# FT2232D.net
KiCad netlist of a schematic drawn in Altium Designer
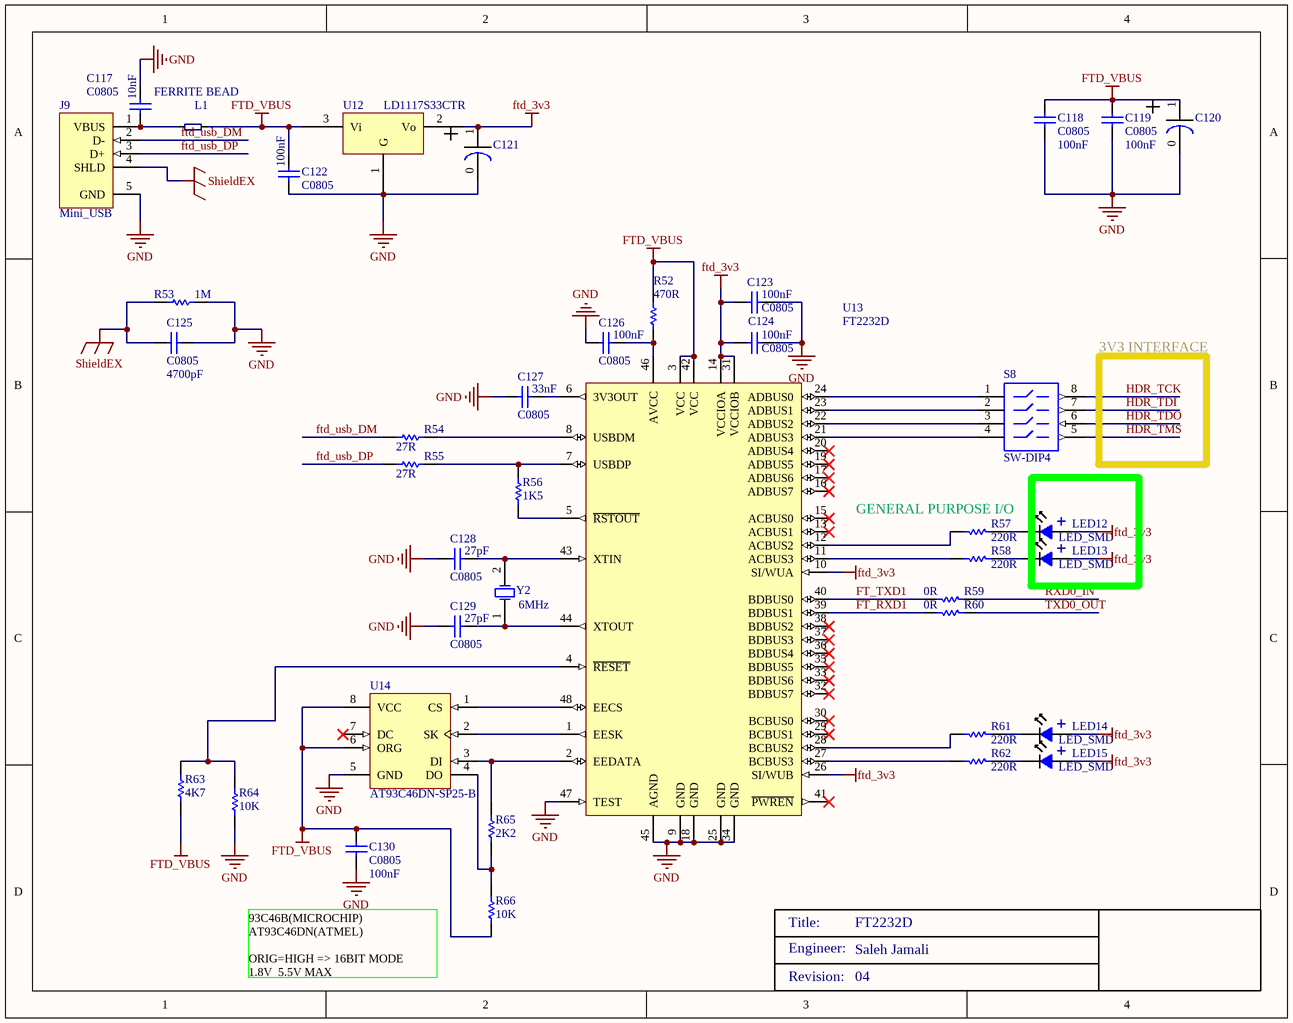
[diagram p0: FT2232D.SchDoc]

(export (version "E")
  (design (tool "Eeschema 10.0.6"))
  (components
    (comp (ref "C117")
      (value "C0805")
      (footprint "0805")
      (description "Ceramic Chip Capacitor - Standard")
      (fields (field (name "ALTIUM_VALUE") "10nF") (field (name "PUBLISHER") "Altium Limited"))
      (libsource (lib "KEMET Chip Capacitor") (part "C0805"))
    )
    (comp (ref "C118")
      (value "C0805")
      (footprint "0805")
      (description "Ceramic Chip Capacitor - Standard")
      (fields (field (name "ALTIUM_VALUE") "100nF") (field (name "PUBLISHER") "Altium Limited"))
      (libsource (lib "KEMET Chip Capacitor") (part "C0805"))
    )
    (comp (ref "C119")
      (value "C0805")
      (footprint "0805")
      (description "Ceramic Chip Capacitor - Standard")
      (fields (field (name "ALTIUM_VALUE") "100nF") (field (name "PUBLISHER") "Altium Limited"))
      (libsource (lib "KEMET Chip Capacitor") (part "C0805"))
    )
    (comp (ref "C120")
      (value "Electrolytic SMD Cap")
      (footprint "22_47u_10A")
      (libsource (lib "SMD_ELECTRLT_CAP") (part "Electrolytic SMD Cap"))
    )
    (comp (ref "C121")
      (value "Electrolytic SMD Cap")
      (footprint "22_47u_10A")
      (libsource (lib "SMD_ELECTRLT_CAP") (part "Electrolytic SMD Cap"))
    )
    (comp (ref "C122")
      (value "C0805")
      (footprint "0805")
      (description "Ceramic Chip Capacitor - Standard")
      (fields (field (name "ALTIUM_VALUE") "100nF") (field (name "PUBLISHER") "Altium Limited"))
      (libsource (lib "KEMET Chip Capacitor") (part "C0805"))
    )
    (comp (ref "C123")
      (value "C0805")
      (footprint "0805")
      (description "Ceramic Chip Capacitor - Standard")
      (fields (field (name "ALTIUM_VALUE") "100nF") (field (name "PUBLISHER") "Altium Limited"))
      (libsource (lib "KEMET Chip Capacitor") (part "C0805"))
    )
    (comp (ref "C124")
      (value "C0805")
      (footprint "0805")
      (description "Ceramic Chip Capacitor - Standard")
      (fields (field (name "ALTIUM_VALUE") "100nF") (field (name "PUBLISHER") "Altium Limited"))
      (libsource (lib "KEMET Chip Capacitor") (part "C0805"))
    )
    (comp (ref "C125")
      (value "C0805")
      (footprint "0805")
      (description "Ceramic Chip Capacitor - Standard")
      (fields (field (name "ALTIUM_VALUE") "4700pF") (field (name "PUBLISHER") "Altium Limited"))
      (libsource (lib "KEMET Chip Capacitor") (part "C0805"))
    )
    (comp (ref "C126")
      (value "C0805")
      (footprint "0805")
      (description "Ceramic Chip Capacitor - Standard")
      (fields (field (name "ALTIUM_VALUE") "100nF") (field (name "PUBLISHER") "Altium Limited"))
      (libsource (lib "KEMET Chip Capacitor") (part "C0805"))
    )
    (comp (ref "C127")
      (value "C0805")
      (footprint "0805")
      (description "Ceramic Chip Capacitor - Standard")
      (fields (field (name "ALTIUM_VALUE") "33nF") (field (name "PUBLISHER") "Altium Limited"))
      (libsource (lib "KEMET Chip Capacitor") (part "C0805"))
    )
    (comp (ref "C128")
      (value "C0805")
      (footprint "0805")
      (description "Ceramic Chip Capacitor - Standard")
      (fields (field (name "ALTIUM_VALUE") "27pF") (field (name "PUBLISHER") "Altium Limited"))
      (libsource (lib "KEMET Chip Capacitor") (part "C0805"))
    )
    (comp (ref "C129")
      (value "C0805")
      (footprint "0805")
      (description "Ceramic Chip Capacitor - Standard")
      (fields (field (name "ALTIUM_VALUE") "27pF") (field (name "PUBLISHER") "Altium Limited"))
      (libsource (lib "KEMET Chip Capacitor") (part "C0805"))
    )
    (comp (ref "C130")
      (value "C0805")
      (footprint "0805")
      (description "Ceramic Chip Capacitor - Standard")
      (fields (field (name "ALTIUM_VALUE") "100nF") (field (name "PUBLISHER") "Altium Limited"))
      (libsource (lib "KEMET Chip Capacitor") (part "C0805"))
    )
    (comp (ref "J9")
      (value "Mini_USB")
      (footprint "My_USB")
      (description "USB 2.0, Right Angle, SMT, B Type, Receptacle, 5 Position, Black")
      (fields (field (name "PUBLISHER") "Altium Limited"))
      (libsource (lib "Mylib") (part "Mini_USB"))
    )
    (comp (ref "L1")
      (value "FERRITE BEAD")
      (footprint "smd_ferrite_1206")
      (libsource (lib "FERRITE_PRJCT") (part "FERRITE BEAD"))
    )
    (comp (ref "LED12")
      (value "LED_SMD")
      (footprint "LED_805")
      (libsource (lib "LED_PRJCT") (part "LED_SMD"))
    )
    (comp (ref "LED13")
      (value "LED_SMD")
      (footprint "LED_805")
      (libsource (lib "LED_PRJCT") (part "LED_SMD"))
    )
    (comp (ref "LED14")
      (value "LED_SMD")
      (footprint "LED_805")
      (libsource (lib "LED_PRJCT") (part "LED_SMD"))
    )
    (comp (ref "LED15")
      (value "LED_SMD")
      (footprint "LED_805")
      (libsource (lib "LED_PRJCT") (part "LED_SMD"))
    )
    (comp (ref "R52")
      (value "470R")
      (footprint "ERA-0805")
      (fields (field (name "PUBLISHER") "Altium Limited"))
      (libsource (lib "Panasonic Resistor") (part "ERA6Y"))
    )
    (comp (ref "R53")
      (value "1M")
      (footprint "ERA-0805")
      (fields (field (name "PUBLISHER") "Altium Limited"))
      (libsource (lib "Panasonic Resistor") (part "ERA6Y"))
    )
    (comp (ref "R54")
      (value "27R")
      (footprint "ERA-0805")
      (fields (field (name "PUBLISHER") "Altium Limited"))
      (libsource (lib "Panasonic Resistor") (part "ERA6Y"))
    )
    (comp (ref "R55")
      (value "27R")
      (footprint "ERA-0805")
      (fields (field (name "PUBLISHER") "Altium Limited"))
      (libsource (lib "Panasonic Resistor") (part "ERA6Y"))
    )
    (comp (ref "R56")
      (value "1K5")
      (footprint "ERA-0805")
      (fields (field (name "PUBLISHER") "Altium Limited"))
      (libsource (lib "Panasonic Resistor") (part "ERA6Y"))
    )
    (comp (ref "R57")
      (value "220R")
      (footprint "ERA-0805")
      (fields (field (name "PUBLISHER") "Altium Limited"))
      (libsource (lib "Panasonic Resistor") (part "ERA6Y"))
    )
    (comp (ref "R58")
      (value "220R")
      (footprint "ERA-0805")
      (fields (field (name "PUBLISHER") "Altium Limited"))
      (libsource (lib "Panasonic Resistor") (part "ERA6Y"))
    )
    (comp (ref "R59")
      (value "0R")
      (footprint "ERA-0805")
      (fields (field (name "PUBLISHER") "Altium Limited"))
      (libsource (lib "Panasonic Resistor") (part "ERA6Y"))
    )
    (comp (ref "R60")
      (value "0R")
      (footprint "ERA-0805")
      (fields (field (name "PUBLISHER") "Altium Limited"))
      (libsource (lib "Panasonic Resistor") (part "ERA6Y"))
    )
    (comp (ref "R61")
      (value "220R")
      (footprint "ERA-0805")
      (fields (field (name "PUBLISHER") "Altium Limited"))
      (libsource (lib "Panasonic Resistor") (part "ERA6Y"))
    )
    (comp (ref "R62")
      (value "220R")
      (footprint "ERA-0805")
      (fields (field (name "PUBLISHER") "Altium Limited"))
      (libsource (lib "Panasonic Resistor") (part "ERA6Y"))
    )
    (comp (ref "R63")
      (value "4K7")
      (footprint "ERA-0805")
      (fields (field (name "PUBLISHER") "Altium Limited"))
      (libsource (lib "Panasonic Resistor") (part "ERA6Y"))
    )
    (comp (ref "R64")
      (value "10K")
      (footprint "ERA-0805")
      (fields (field (name "PUBLISHER") "Altium Limited"))
      (libsource (lib "Panasonic Resistor") (part "ERA6Y"))
    )
    (comp (ref "R65")
      (value "2K2")
      (footprint "ERA-0805")
      (fields (field (name "PUBLISHER") "Altium Limited"))
      (libsource (lib "Panasonic Resistor") (part "ERA6Y"))
    )
    (comp (ref "R66")
      (value "10K")
      (footprint "ERA-0805")
      (fields (field (name "PUBLISHER") "Altium Limited"))
      (libsource (lib "Panasonic Resistor") (part "ERA6Y"))
    )
    (comp (ref "S8")
      (value "SW-DIP4")
      (footprint "DIP-8")
      (description "DIP Switch")
      (fields (field (name "PUBLISHER") "Altium Limited"))
      (libsource (lib "Miscellaneous Devices") (part "SW-DIP4"))
    )
    (comp (ref "U12")
      (value "LD1117S33CTR")
      (footprint "SOT223")
      (description "2.5 volt, 800mA Regulator")
      (libsource (lib "LD1117S25_SOT223") (part "LD1117S33CTR"))
    )
    (comp (ref "U13")
      (value "FT2232D")
      (footprint "LQFP-48_M")
      (description "FT2232D Dual USB to Serial UART/FIFO IC, -40 to +85 degC, 48-pin LQFP")
      (fields (field (name "MANUFACTURER") "FTDI"))
      (libsource (lib "FTDI FT Series") (part "FT2232D"))
    )
    (comp (ref "U14")
      (value "AT93C46DN-SP25-B")
      (footprint "8S1_M")
      (description "1Kbit (128 x 8 or 64 x 16), 3-wire Bus Serial Automotive EEPROM, 2.5V, 8-Pin SOIC, Bulk")
      (libsource (lib "Atmel Serial EEPROM") (part "AT93C46DN-SP25-B"))
    )
    (comp (ref "Y2")
      (value "6MHz")
      (footprint "HC-49U")
      (description "Crystal Oscillator")
      (fields (field (name "PUBLISHER") "Altium Limited"))
      (libsource (lib "ECS Crystal Oscillator") (part "ECS-18-13-1"))
    )
  )
  (nets
    (net (code "1") (name "/FT_RXD1") (class "Default")
      (node (ref "R60") (pin "2") (pinfunction "2_2") (pintype "passive"))
      (node (ref "U13") (pin "39") (pinfunction "BDBUS1_39") (pintype "bidirectional"))
    )
    (net (code "2") (name "/FT_TXD1") (class "Default")
      (node (ref "R59") (pin "2") (pinfunction "2_2") (pintype "passive"))
      (node (ref "U13") (pin "40") (pinfunction "BDBUS0_40") (pintype "bidirectional"))
    )
    (net (code "3") (name "/HDR_TCK") (class "Default")
      (node (ref "S8") (pin "8") (pinfunction "8_8") (pintype "output"))
    )
    (net (code "4") (name "/HDR_TDI") (class "Default")
      (node (ref "S8") (pin "7") (pinfunction "7_7") (pintype "output"))
    )
    (net (code "5") (name "/HDR_TDO") (class "Default")
      (node (ref "S8") (pin "6") (pinfunction "6_6") (pintype "input"))
    )
    (net (code "6") (name "/HDR_TMS") (class "Default")
      (node (ref "S8") (pin "5") (pinfunction "5_5") (pintype "output"))
    )
    (net (code "7") (name "/RXD0_IN") (class "Default")
      (node (ref "R59") (pin "1") (pinfunction "1_1") (pintype "passive"))
    )
    (net (code "8") (name "/TXD0_OUT") (class "Default")
      (node (ref "R60") (pin "1") (pinfunction "1_1") (pintype "passive"))
    )
    (net (code "9") (name "/ftd_usb_DM") (class "Default")
      (node (ref "J9") (pin "2") (pinfunction "D-_2") (pintype "input"))
      (node (ref "R54") (pin "2") (pinfunction "2_2") (pintype "passive"))
    )
    (net (code "10") (name "/ftd_usb_DP") (class "Default")
      (node (ref "J9") (pin "3") (pinfunction "D+_3") (pintype "input"))
      (node (ref "R55") (pin "2") (pinfunction "2_2") (pintype "passive"))
    )
    (net (code "11") (name "FTD_VBUS") (class "Default")
      (node (ref "C118") (pin "2") (pinfunction "2_2") (pintype "passive"))
      (node (ref "C119") (pin "2") (pinfunction "2_2") (pintype "passive"))
      (node (ref "C120") (pin "1") (pinfunction "1_1") (pintype "passive"))
      (node (ref "C122") (pin "1") (pinfunction "1_1") (pintype "passive"))
      (node (ref "C130") (pin "2") (pinfunction "2_2") (pintype "passive"))
      (node (ref "L1") (pin "1") (pinfunction "1_1") (pintype "passive"))
      (node (ref "R52") (pin "1") (pinfunction "1_1") (pintype "passive"))
      (node (ref "R63") (pin "1") (pinfunction "1_1") (pintype "passive"))
      (node (ref "R66") (pin "1") (pinfunction "1_1") (pintype "passive"))
      (node (ref "U12") (pin "3") (pinfunction "Vi_3") (pintype "power_in"))
      (node (ref "U13") (pin "3") (pinfunction "VCC_3") (pintype "power_in"))
      (node (ref "U13") (pin "42") (pinfunction "VCC_42") (pintype "power_in"))
      (node (ref "U14") (pin "6") (pinfunction "ORG_6") (pintype "input"))
      (node (ref "U14") (pin "8") (pinfunction "VCC_8") (pintype "power_in"))
    )
    (net (code "12") (name "GND") (class "Default")
      (node (ref "C117") (pin "1") (pinfunction "1_1") (pintype "passive"))
      (node (ref "C118") (pin "1") (pinfunction "1_1") (pintype "passive"))
      (node (ref "C119") (pin "1") (pinfunction "1_1") (pintype "passive"))
      (node (ref "C120") (pin "0") (pinfunction "0_0") (pintype "passive"))
      (node (ref "C121") (pin "0") (pinfunction "0_0") (pintype "passive"))
      (node (ref "C122") (pin "2") (pinfunction "2_2") (pintype "passive"))
      (node (ref "C123") (pin "2") (pinfunction "2_2") (pintype "passive"))
      (node (ref "C124") (pin "2") (pinfunction "2_2") (pintype "passive"))
      (node (ref "C125") (pin "2") (pinfunction "2_2") (pintype "passive"))
      (node (ref "C126") (pin "1") (pinfunction "1_1") (pintype "passive"))
      (node (ref "C127") (pin "1") (pinfunction "1_1") (pintype "passive"))
      (node (ref "C128") (pin "1") (pinfunction "1_1") (pintype "passive"))
      (node (ref "C129") (pin "1") (pinfunction "1_1") (pintype "passive"))
      (node (ref "C130") (pin "1") (pinfunction "1_1") (pintype "passive"))
      (node (ref "J9") (pin "5") (pinfunction "GND_5") (pintype "passive"))
      (node (ref "R53") (pin "1") (pinfunction "1_1") (pintype "passive"))
      (node (ref "R64") (pin "1") (pinfunction "1_1") (pintype "passive"))
      (node (ref "U12") (pin "1") (pinfunction "G_1") (pintype "power_in"))
      (node (ref "U13") (pin "18") (pinfunction "GND_18") (pintype "power_in"))
      (node (ref "U13") (pin "25") (pinfunction "GND_25") (pintype "power_in"))
      (node (ref "U13") (pin "34") (pinfunction "GND_34") (pintype "power_in"))
      (node (ref "U13") (pin "45") (pinfunction "AGND_45") (pintype "power_in"))
      (node (ref "U13") (pin "47") (pinfunction "TEST_47") (pintype "input"))
      (node (ref "U13") (pin "9") (pinfunction "GND_9") (pintype "power_in"))
      (node (ref "U14") (pin "5") (pinfunction "GND_5") (pintype "power_in"))
    )
    (net (code "13") (name "Net-(J9-VBUS)") (class "Default")
      (node (ref "C117") (pin "2") (pinfunction "2_2") (pintype "passive"))
      (node (ref "J9") (pin "1") (pinfunction "VBUS_1") (pintype "power_in"))
      (node (ref "L1") (pin "0") (pinfunction "0_0") (pintype "passive"))
    )
    (net (code "14") (name "Net-(LED12-Pad2)") (class "Default")
      (node (ref "LED12") (pin "2") (pinfunction "2_2") (pintype "passive"))
      (node (ref "R57") (pin "1") (pinfunction "1_1") (pintype "passive"))
    )
    (net (code "15") (name "Net-(LED13-Pad2)") (class "Default")
      (node (ref "LED13") (pin "2") (pinfunction "2_2") (pintype "passive"))
      (node (ref "R58") (pin "1") (pinfunction "1_1") (pintype "passive"))
    )
    (net (code "16") (name "Net-(LED14-Pad2)") (class "Default")
      (node (ref "LED14") (pin "2") (pinfunction "2_2") (pintype "passive"))
      (node (ref "R61") (pin "1") (pinfunction "1_1") (pintype "passive"))
    )
    (net (code "17") (name "Net-(LED15-Pad2)") (class "Default")
      (node (ref "LED15") (pin "2") (pinfunction "2_2") (pintype "passive"))
      (node (ref "R62") (pin "1") (pinfunction "1_1") (pintype "passive"))
    )
    (net (code "18") (name "Net-(U13-3V3OUT)") (class "Default")
      (node (ref "C127") (pin "2") (pinfunction "2_2") (pintype "passive"))
      (node (ref "U13") (pin "6") (pinfunction "3V3OUT_6") (pintype "output"))
    )
    (net (code "19") (name "Net-(U13-ACBUS2)") (class "Default")
      (node (ref "R57") (pin "2") (pinfunction "2_2") (pintype "passive"))
      (node (ref "U13") (pin "12") (pinfunction "ACBUS2_12") (pintype "bidirectional"))
    )
    (net (code "20") (name "Net-(U13-ACBUS3)") (class "Default")
      (node (ref "R58") (pin "2") (pinfunction "2_2") (pintype "passive"))
      (node (ref "U13") (pin "11") (pinfunction "ACBUS3_11") (pintype "bidirectional"))
    )
    (net (code "21") (name "Net-(U13-ADBUS0)") (class "Default")
      (node (ref "S8") (pin "1") (pinfunction "1_1") (pintype "passive"))
      (node (ref "U13") (pin "24") (pinfunction "ADBUS0_24") (pintype "bidirectional"))
    )
    (net (code "22") (name "Net-(U13-ADBUS1)") (class "Default")
      (node (ref "S8") (pin "2") (pinfunction "2_2") (pintype "passive"))
      (node (ref "U13") (pin "23") (pinfunction "ADBUS1_23") (pintype "bidirectional"))
    )
    (net (code "23") (name "Net-(U13-ADBUS2)") (class "Default")
      (node (ref "S8") (pin "3") (pinfunction "3_3") (pintype "passive"))
      (node (ref "U13") (pin "22") (pinfunction "ADBUS2_22") (pintype "bidirectional"))
    )
    (net (code "24") (name "Net-(U13-ADBUS3)") (class "Default")
      (node (ref "S8") (pin "4") (pinfunction "4_4") (pintype "passive"))
      (node (ref "U13") (pin "21") (pinfunction "ADBUS3_21") (pintype "bidirectional"))
    )
    (net (code "25") (name "Net-(U13-AVCC)") (class "Default")
      (node (ref "C126") (pin "2") (pinfunction "2_2") (pintype "passive"))
      (node (ref "R52") (pin "2") (pinfunction "2_2") (pintype "passive"))
      (node (ref "U13") (pin "46") (pinfunction "AVCC_46") (pintype "power_in"))
    )
    (net (code "26") (name "Net-(U13-BCBUS2)") (class "Default")
      (node (ref "R61") (pin "2") (pinfunction "2_2") (pintype "passive"))
      (node (ref "U13") (pin "28") (pinfunction "BCBUS2_28") (pintype "bidirectional"))
    )
    (net (code "27") (name "Net-(U13-BCBUS3)") (class "Default")
      (node (ref "R62") (pin "2") (pinfunction "2_2") (pintype "passive"))
      (node (ref "U13") (pin "27") (pinfunction "BCBUS3_27") (pintype "bidirectional"))
    )
    (net (code "28") (name "Net-(U13-EECS)") (class "Default")
      (node (ref "U13") (pin "48") (pinfunction "EECS_48") (pintype "bidirectional"))
      (node (ref "U14") (pin "1") (pinfunction "CS_1") (pintype "input"))
    )
    (net (code "29") (name "Net-(U13-EEDATA)") (class "Default")
      (node (ref "R65") (pin "2") (pinfunction "2_2") (pintype "passive"))
      (node (ref "U13") (pin "2") (pinfunction "EEDATA_2") (pintype "bidirectional"))
      (node (ref "U14") (pin "3") (pinfunction "DI_3") (pintype "input"))
    )
    (net (code "30") (name "Net-(U13-EESK)") (class "Default")
      (node (ref "U13") (pin "1") (pinfunction "EESK_1") (pintype "output"))
      (node (ref "U14") (pin "2") (pinfunction "SK_2") (pintype "input"))
    )
    (net (code "31") (name "Net-(U13-USBDM)") (class "Default")
      (node (ref "R54") (pin "1") (pinfunction "1_1") (pintype "passive"))
      (node (ref "U13") (pin "8") (pinfunction "USBDM_8") (pintype "bidirectional"))
    )
    (net (code "32") (name "Net-(U13-USBDP)") (class "Default")
      (node (ref "R55") (pin "1") (pinfunction "1_1") (pintype "passive"))
      (node (ref "R56") (pin "2") (pinfunction "2_2") (pintype "passive"))
      (node (ref "U13") (pin "7") (pinfunction "USBDP_7") (pintype "bidirectional"))
    )
    (net (code "33") (name "Net-(U13-XTIN)") (class "Default")
      (node (ref "C128") (pin "2") (pinfunction "2_2") (pintype "passive"))
      (node (ref "U13") (pin "43") (pinfunction "XTIN_43") (pintype "input"))
      (node (ref "Y2") (pin "2") (pinfunction "OSC2_2") (pintype "passive"))
    )
    (net (code "34") (name "Net-(U13-XTOUT)") (class "Default")
      (node (ref "C129") (pin "2") (pinfunction "2_2") (pintype "passive"))
      (node (ref "U13") (pin "44") (pinfunction "XTOUT_44") (pintype "output"))
      (node (ref "Y2") (pin "1") (pinfunction "OSC1_1") (pintype "passive"))
    )
    (net (code "35") (name "Net-(U13-~{RESET})") (class "Default")
      (node (ref "R63") (pin "2") (pinfunction "2_2") (pintype "passive"))
      (node (ref "R64") (pin "2") (pinfunction "2_2") (pintype "passive"))
      (node (ref "U13") (pin "4") (pinfunction "~{RESET}_4") (pintype "input"))
    )
    (net (code "36") (name "Net-(U13-~{RSTOUT})") (class "Default")
      (node (ref "R56") (pin "1") (pinfunction "1_1") (pintype "passive"))
      (node (ref "U13") (pin "5") (pinfunction "~{RSTOUT}_5") (pintype "output"))
    )
    (net (code "37") (name "Net-(U14-DO)") (class "Default")
      (node (ref "R65") (pin "1") (pinfunction "1_1") (pintype "passive"))
      (node (ref "R66") (pin "2") (pinfunction "2_2") (pintype "passive"))
      (node (ref "U14") (pin "4") (pinfunction "DO_4") (pintype "tri_state"))
    )
    (net (code "38") (name "ShieldEX") (class "Default")
      (node (ref "C125") (pin "1") (pinfunction "1_1") (pintype "passive"))
      (node (ref "J9") (pin "4") (pinfunction "SHLD_4") (pintype "power_in"))
      (node (ref "R53") (pin "2") (pinfunction "2_2") (pintype "passive"))
    )
    (net (code "39") (name "ftd_3v3") (class "Default")
      (node (ref "C121") (pin "1") (pinfunction "1_1") (pintype "passive"))
      (node (ref "C123") (pin "1") (pinfunction "1_1") (pintype "passive"))
      (node (ref "C124") (pin "1") (pinfunction "1_1") (pintype "passive"))
      (node (ref "LED12") (pin "1") (pinfunction "1_1") (pintype "passive"))
      (node (ref "LED13") (pin "1") (pinfunction "1_1") (pintype "passive"))
      (node (ref "LED14") (pin "1") (pinfunction "1_1") (pintype "passive"))
      (node (ref "LED15") (pin "1") (pinfunction "1_1") (pintype "passive"))
      (node (ref "U12") (pin "2") (pinfunction "Vo_2") (pintype "power_in"))
      (node (ref "U13") (pin "10") (pinfunction "SI/WUA_10") (pintype "input"))
      (node (ref "U13") (pin "14") (pinfunction "VCCIOA_14") (pintype "power_in"))
      (node (ref "U13") (pin "26") (pinfunction "SI/WUB_26") (pintype "input"))
      (node (ref "U13") (pin "31") (pinfunction "VCCIOB_31") (pintype "power_in"))
    )
    (net (code "40") (name "unconnected-(U13-ACBUS0-Pad15)") (class "Default")
      (node (ref "U13") (pin "15") (pinfunction "ACBUS0_15") (pintype "bidirectional+no_connect"))
    )
    (net (code "41") (name "unconnected-(U13-ACBUS1-Pad13)") (class "Default")
      (node (ref "U13") (pin "13") (pinfunction "ACBUS1_13") (pintype "bidirectional+no_connect"))
    )
    (net (code "42") (name "unconnected-(U13-ADBUS4-Pad20)") (class "Default")
      (node (ref "U13") (pin "20") (pinfunction "ADBUS4_20") (pintype "bidirectional+no_connect"))
    )
    (net (code "43") (name "unconnected-(U13-ADBUS5-Pad19)") (class "Default")
      (node (ref "U13") (pin "19") (pinfunction "ADBUS5_19") (pintype "bidirectional+no_connect"))
    )
    (net (code "44") (name "unconnected-(U13-ADBUS6-Pad17)") (class "Default")
      (node (ref "U13") (pin "17") (pinfunction "ADBUS6_17") (pintype "bidirectional+no_connect"))
    )
    (net (code "45") (name "unconnected-(U13-ADBUS7-Pad16)") (class "Default")
      (node (ref "U13") (pin "16") (pinfunction "ADBUS7_16") (pintype "bidirectional+no_connect"))
    )
    (net (code "46") (name "unconnected-(U13-BCBUS0-Pad30)") (class "Default")
      (node (ref "U13") (pin "30") (pinfunction "BCBUS0_30") (pintype "bidirectional+no_connect"))
    )
    (net (code "47") (name "unconnected-(U13-BCBUS1-Pad29)") (class "Default")
      (node (ref "U13") (pin "29") (pinfunction "BCBUS1_29") (pintype "bidirectional+no_connect"))
    )
    (net (code "48") (name "unconnected-(U13-BDBUS2-Pad38)") (class "Default")
      (node (ref "U13") (pin "38") (pinfunction "BDBUS2_38") (pintype "bidirectional+no_connect"))
    )
    (net (code "49") (name "unconnected-(U13-BDBUS3-Pad37)") (class "Default")
      (node (ref "U13") (pin "37") (pinfunction "BDBUS3_37") (pintype "bidirectional+no_connect"))
    )
    (net (code "50") (name "unconnected-(U13-BDBUS4-Pad36)") (class "Default")
      (node (ref "U13") (pin "36") (pinfunction "BDBUS4_36") (pintype "bidirectional+no_connect"))
    )
    (net (code "51") (name "unconnected-(U13-BDBUS5-Pad35)") (class "Default")
      (node (ref "U13") (pin "35") (pinfunction "BDBUS5_35") (pintype "bidirectional+no_connect"))
    )
    (net (code "52") (name "unconnected-(U13-BDBUS6-Pad33)") (class "Default")
      (node (ref "U13") (pin "33") (pinfunction "BDBUS6_33") (pintype "bidirectional+no_connect"))
    )
    (net (code "53") (name "unconnected-(U13-BDBUS7-Pad32)") (class "Default")
      (node (ref "U13") (pin "32") (pinfunction "BDBUS7_32") (pintype "bidirectional+no_connect"))
    )
    (net (code "54") (name "unconnected-(U13-~{PWREN}-Pad41)") (class "Default")
      (node (ref "U13") (pin "41") (pinfunction "~{PWREN}_41") (pintype "output+no_connect"))
    )
    (net (code "55") (name "unconnected-(U14-DC-Pad7)") (class "Default")
      (node (ref "U14") (pin "7") (pinfunction "DC_7") (pintype "input+no_connect"))
    )
  )
)
